# SCH_pap01_2022-05-10.net
KiCad netlist of a schematic drawn in EasyEDA
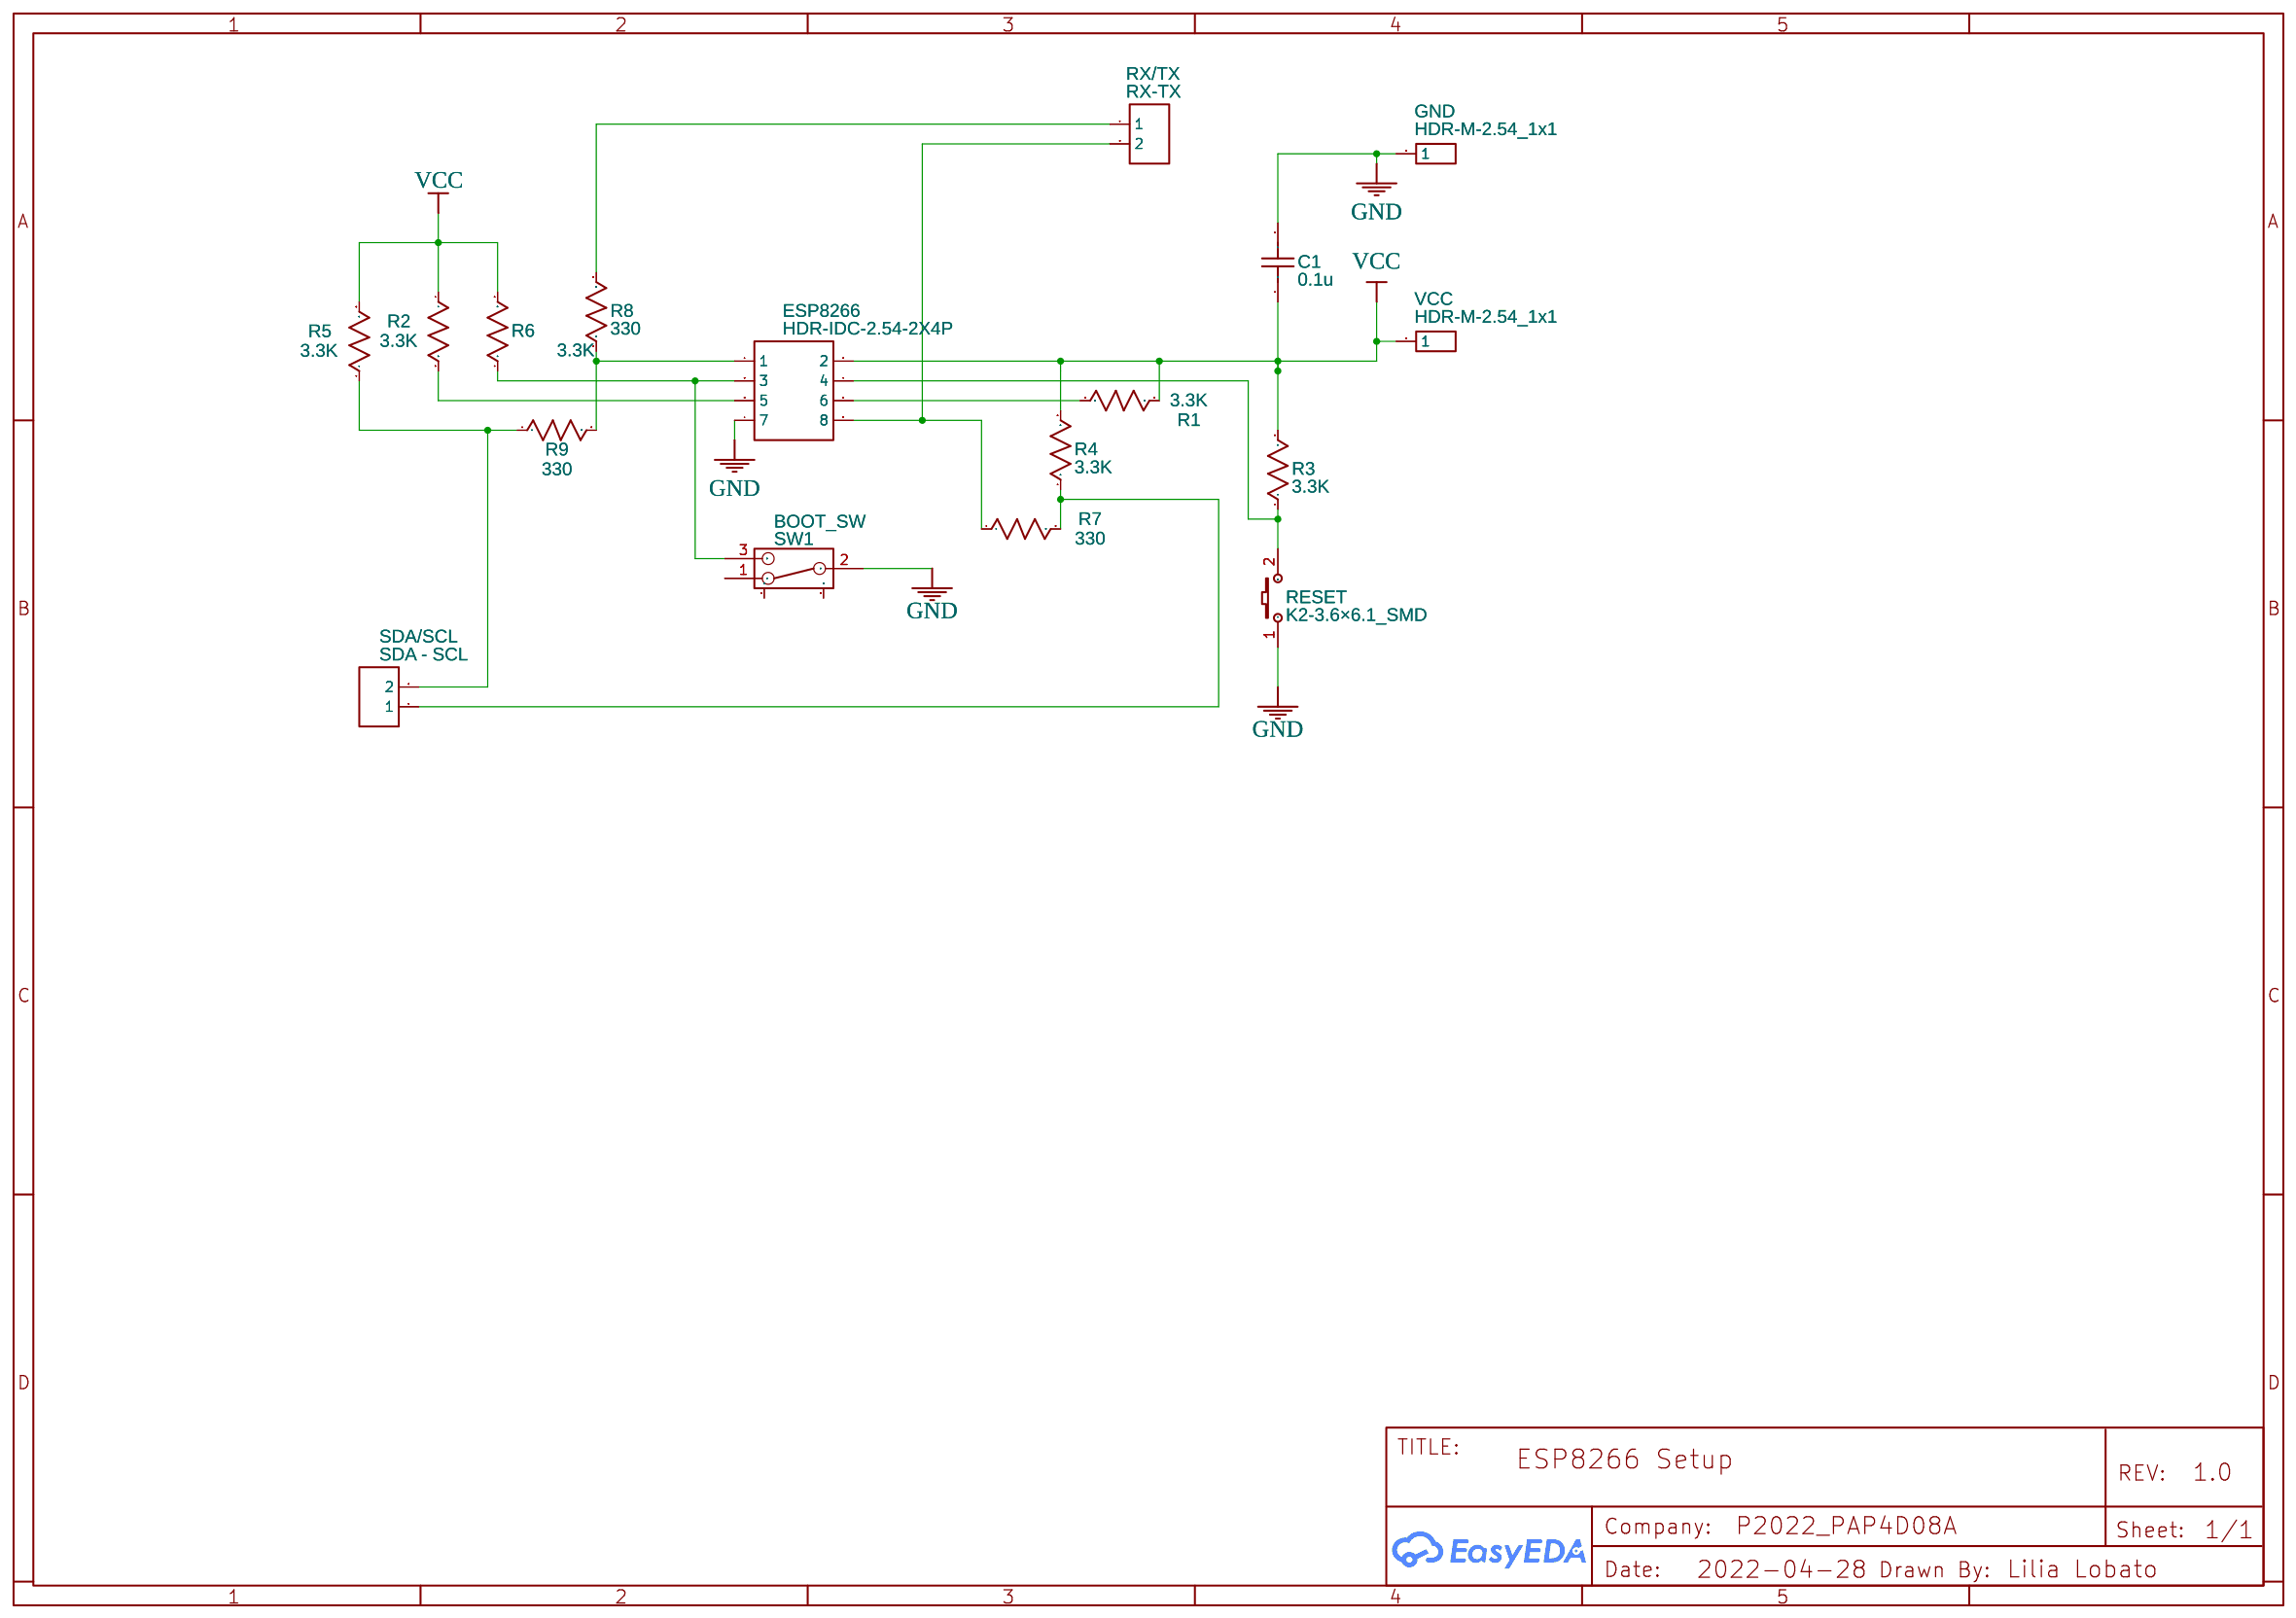
[diagram p0: schematic sheet]

(export (version "E")
  (design (tool "Eeschema 10.0.6"))
  (components
    (comp (ref "C1") (value "0.1u") (libsource (lib "") (part "C_0603_US")))
    (comp (ref "ESP8266")
      (value "HDR-IDC-2.54-2X4P")
      (fields
        (field (name "BOM_Manufacturer Part") "IDC Box 2X4 2.54MM")
        (field (name "BOM_Supplier Part") "C9135")
      )
      (libsource (lib "") (part "HDR-IDC-2.54-2X4P"))
    )
    (comp (ref "GND")
      (value "HDR-M-2.54_1x1")
      (fields (field (name "BOM_Supplier Part") "C81276"))
      (libsource (lib "") (part "HDR-M-2.54_1x1"))
    )
    (comp (ref "R1") (value "3.3K") (libsource (lib "") (part "R_0603_US_1")))
    (comp (ref "R2") (value "3.3K") (libsource (lib "") (part "R_0603_US_3")))
    (comp (ref "R3") (value "3.3K") (libsource (lib "") (part "R_0603_US")))
    (comp (ref "R4") (value "3.3K") (libsource (lib "") (part "R_0603_US")))
    (comp (ref "R5") (value "3.3K") (libsource (lib "") (part "R_0603_US")))
    (comp (ref "R6") (value "3.3K") (libsource (lib "") (part "R_0603_US")))
    (comp (ref "R7") (value "330") (libsource (lib "") (part "R_0603_US_2")))
    (comp (ref "R8") (value "330") (libsource (lib "") (part "R_0603_US")))
    (comp (ref "R9") (value "330") (libsource (lib "") (part "R_0603_US_2")))
    (comp (ref "RESET")
      (value "K2-3.6×6.1_SMD")
      (fields
        (field (name "BOM_Manufacturer Part") "K2-1107ST-A4SW-06")
        (field (name "BOM_Supplier Part") "C118141")
      )
      (libsource (lib "") (part "K2-3.6×6.1_SMD"))
    )
    (comp (ref "RX/TX")
      (value "RX-TX")
      (fields (field (name "BOM_Supplier Part") "C49661"))
      (libsource (lib "") (part "HDR-F-2.54_1x2_1"))
    )
    (comp (ref "SDA/SCL")
      (value "SDA - SCL")
      (fields (field (name "BOM_Supplier Part") "C49661"))
      (libsource (lib "") (part "HDR-F-2.54_1x2"))
    )
    (comp (ref "SW1")
      (value "BOOT_SW")
      (fields
        (field (name "BOM_Manufacturer Part") "SS-12D02-VG4")
        (field (name "BOM_Supplier Part") "C136719")
      )
      (libsource (lib "") (part "SS-12D02-VG4"))
    )
    (comp (ref "VCC")
      (value "HDR-M-2.54_1x1")
      (fields (field (name "BOM_Supplier Part") "C81276"))
      (libsource (lib "") (part "HDR-M-2.54_1x1_1"))
    )
  )
  (nets
    (net (code "1") (name "GND") (class "Default")
      (node (ref "C1") (pin "2") (pinfunction "2_2") (pintype "unspecified"))
      (node (ref "ESP8266") (pin "7") (pinfunction "7_7") (pintype "unspecified"))
      (node (ref "GND") (pin "1") (pinfunction "1_1") (pintype "input"))
      (node (ref "RESET") (pin "1") (pinfunction "1_1") (pintype "unspecified"))
      (node (ref "SW1") (pin "2") (pinfunction "2_2") (pintype "unspecified"))
    )
    (net (code "2") (name "Net-(ESP8266-Pad1)") (class "Default")
      (node (ref "ESP8266") (pin "1") (pinfunction "1_1") (pintype "unspecified"))
      (node (ref "R8") (pin "1") (pinfunction "1_1") (pintype "unspecified"))
      (node (ref "R9") (pin "2") (pinfunction "2_2") (pintype "unspecified"))
    )
    (net (code "3") (name "Net-(ESP8266-Pad3)") (class "Default")
      (node (ref "ESP8266") (pin "3") (pinfunction "3_3") (pintype "unspecified"))
      (node (ref "R6") (pin "1") (pinfunction "1_1") (pintype "unspecified"))
      (node (ref "SW1") (pin "3") (pinfunction "3_3") (pintype "unspecified"))
    )
    (net (code "4") (name "Net-(ESP8266-Pad4)") (class "Default")
      (node (ref "ESP8266") (pin "4") (pinfunction "4_4") (pintype "unspecified"))
      (node (ref "R3") (pin "1") (pinfunction "1_1") (pintype "unspecified"))
      (node (ref "RESET") (pin "2") (pinfunction "2_2") (pintype "unspecified"))
    )
    (net (code "5") (name "Net-(ESP8266-Pad5)") (class "Default")
      (node (ref "ESP8266") (pin "5") (pinfunction "5_5") (pintype "unspecified"))
      (node (ref "R2") (pin "2") (pinfunction "2_2") (pintype "unspecified"))
    )
    (net (code "6") (name "Net-(ESP8266-Pad6)") (class "Default")
      (node (ref "ESP8266") (pin "6") (pinfunction "6_6") (pintype "unspecified"))
      (node (ref "R1") (pin "2") (pinfunction "2_2") (pintype "unspecified"))
    )
    (net (code "7") (name "Net-(ESP8266-Pad8)") (class "Default")
      (node (ref "ESP8266") (pin "8") (pinfunction "8_8") (pintype "unspecified"))
      (node (ref "R7") (pin "1") (pinfunction "1_1") (pintype "unspecified"))
      (node (ref "RX/TX") (pin "2") (pinfunction "2_2") (pintype "input"))
    )
    (net (code "8") (name "Net-(R4-Pad1)") (class "Default")
      (node (ref "R4") (pin "1") (pinfunction "1_1") (pintype "unspecified"))
      (node (ref "R7") (pin "2") (pinfunction "2_2") (pintype "unspecified"))
      (node (ref "SDA/SCL") (pin "1") (pinfunction "1_1") (pintype "input"))
    )
    (net (code "9") (name "Net-(R5-Pad1)") (class "Default")
      (node (ref "R5") (pin "1") (pinfunction "1_1") (pintype "unspecified"))
      (node (ref "R9") (pin "1") (pinfunction "1_1") (pintype "unspecified"))
      (node (ref "SDA/SCL") (pin "2") (pinfunction "2_2") (pintype "input"))
    )
    (net (code "10") (name "Net-(R8-Pad2)") (class "Default")
      (node (ref "R8") (pin "2") (pinfunction "2_2") (pintype "unspecified"))
      (node (ref "RX/TX") (pin "1") (pinfunction "1_1") (pintype "input"))
    )
    (net (code "11") (name "VCC") (class "Default")
      (node (ref "C1") (pin "1") (pinfunction "1_1") (pintype "unspecified"))
      (node (ref "ESP8266") (pin "2") (pinfunction "2_2") (pintype "unspecified"))
      (node (ref "R1") (pin "1") (pinfunction "1_1") (pintype "unspecified"))
      (node (ref "R2") (pin "1") (pinfunction "1_1") (pintype "unspecified"))
      (node (ref "R3") (pin "2") (pinfunction "2_2") (pintype "unspecified"))
      (node (ref "R4") (pin "2") (pinfunction "2_2") (pintype "unspecified"))
      (node (ref "R5") (pin "2") (pinfunction "2_2") (pintype "unspecified"))
      (node (ref "R6") (pin "2") (pinfunction "2_2") (pintype "unspecified"))
      (node (ref "VCC") (pin "1") (pinfunction "1_1") (pintype "input"))
    )
    (net (code "12") (name "unconnected-(SW1-Pad1)") (class "Default")
      (node (ref "SW1") (pin "1") (pinfunction "1_1") (pintype "unspecified"))
    )
    (net (code "13") (name "unconnected-(SW1-Pad4)") (class "Default")
      (node (ref "SW1") (pin "4") (pinfunction "4_4") (pintype "unspecified"))
    )
    (net (code "14") (name "unconnected-(SW1-Pad5)") (class "Default")
      (node (ref "SW1") (pin "5") (pinfunction "5_5") (pintype "unspecified"))
    )
  )
)
